# ToneControl-BC547.net
KiCad netlist of a schematic drawn in EAGLE
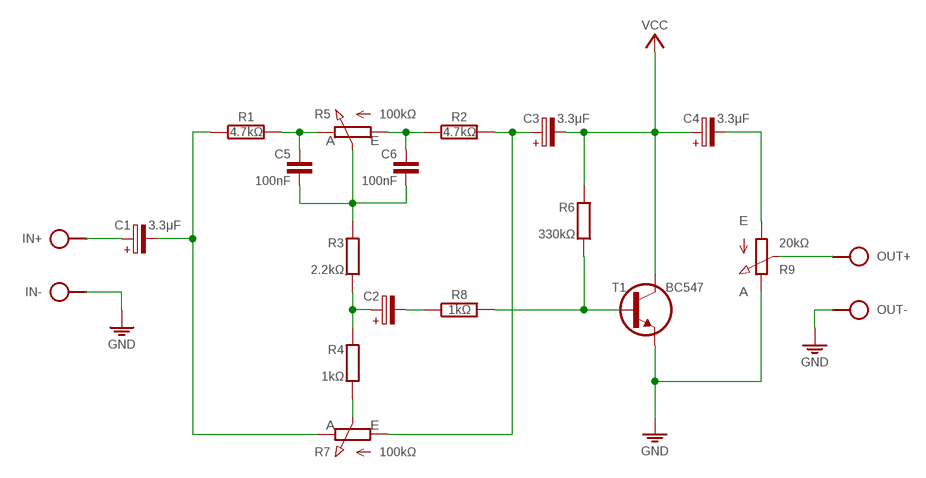
[diagram p0: schematic, sheet 1]

(export (version "E")
  (design (tool "Eeschema 10.0.6"))
  (components
    (comp (ref "C1")
      (value "3.3μF")
      (footprint "eagle-import:E2,5-3")
      (libsource (lib "eagle-import") (part "CPOL-HE2,5-3"))
    )
    (comp (ref "C2")
      (value "CPOL-HE2,5-3")
      (footprint "eagle-import:E2,5-3")
      (libsource (lib "eagle-import") (part "CPOL-HE2,5-3"))
    )
    (comp (ref "C3")
      (value "3.3μF")
      (footprint "eagle-import:E2,5-3")
      (libsource (lib "eagle-import") (part "CPOL-HE2,5-3"))
    )
    (comp (ref "C4")
      (value "3.3μF")
      (footprint "eagle-import:E2,5-3")
      (libsource (lib "eagle-import") (part "CPOL-HE2,5-3"))
    )
    (comp (ref "C5")
      (value "100nF")
      (footprint "eagle-import:C050-020X044_V")
      (libsource (lib "eagle-import") (part "C050-020X044/V"))
    )
    (comp (ref "C6")
      (value "100nF")
      (footprint "eagle-import:C050-020X044_V")
      (libsource (lib "eagle-import") (part "C050-020X044/V"))
    )
    (comp (ref "IN")
      (value "SPAD+--+")
      (footprint "eagle-import:SPAD-+")
      (libsource (lib "eagle-import") (part "SPAD+--+"))
    )
    (comp (ref "OUT")
      (value "SPAD+-+-")
      (footprint "eagle-import:SPAD+-")
      (libsource (lib "eagle-import") (part "SPAD+-+-"))
    )
    (comp (ref "R1")
      (value "4.7kΩ")
      (footprint "eagle-import:0204_10")
      (libsource (lib "eagle-import") (part "R-H0204/10"))
    )
    (comp (ref "R2")
      (value "4.7kΩ")
      (footprint "eagle-import:0204_10")
      (libsource (lib "eagle-import") (part "R-H0204/10"))
    )
    (comp (ref "R3")
      (value "2.2kΩ")
      (footprint "eagle-import:0204_10-V")
      (libsource (lib "eagle-import") (part "R0204/10-V"))
    )
    (comp (ref "R4")
      (value "1kΩ")
      (footprint "eagle-import:0204_10-V")
      (libsource (lib "eagle-import") (part "R0204/10-V"))
    )
    (comp (ref "R5")
      (value "100kΩ")
      (footprint "eagle-import:POT")
      (libsource (lib "eagle-import") (part "POT-H"))
    )
    (comp (ref "R6")
      (value "330kΩ")
      (footprint "eagle-import:0204_10-V")
      (libsource (lib "eagle-import") (part "R0204/10-V"))
    )
    (comp (ref "R7")
      (value "100kΩ")
      (footprint "eagle-import:POT")
      (libsource (lib "eagle-import") (part "POT-H"))
    )
    (comp (ref "R8")
      (value "1kΩ")
      (footprint "eagle-import:0204_10")
      (libsource (lib "eagle-import") (part "R-H0204/10"))
    )
    (comp (ref "R9")
      (value "20kΩ")
      (footprint "eagle-import:POT")
      (libsource (lib "eagle-import") (part "POT"))
    )
    (comp (ref "S1")
      (value "VCC_GNDR")
      (footprint "eagle-import:SPAD+-")
      (libsource (lib "eagle-import") (part "VCC_GNDR"))
    )
    (comp (ref "T1")
      (value "BC547")
      (footprint "eagle-import:TO92-CBE")
      (libsource (lib "eagle-import") (part "BC547CBE"))
    )
  )
  (nets
    (net (code "1") (name "GND") (class "Default")
      (node (ref "IN") (pin "1") (pinfunction "P$1_1") (pintype "passive"))
      (node (ref "OUT") (pin "1") (pinfunction "P$1_1") (pintype "passive"))
      (node (ref "R9") (pin "E") (pinfunction "E_E") (pintype "passive"))
      (node (ref "S1") (pin "1") (pinfunction "GND_1") (pintype "power_in"))
      (node (ref "T1") (pin "E") (pinfunction "E_E") (pintype "passive"))
    )
    (net (code "2") (name "Net-(C1-Pad-)") (class "Default")
      (node (ref "C1") (pin "-") (pinfunction "-_-") (pintype "passive"))
      (node (ref "R1") (pin "1") (pinfunction "1_1") (pintype "passive"))
      (node (ref "R7") (pin "E") (pinfunction "E_E") (pintype "passive"))
    )
    (net (code "3") (name "Net-(C2-Pad+)") (class "Default")
      (node (ref "C2") (pin "+") (pinfunction "+_+") (pintype "passive"))
      (node (ref "R3") (pin "2") (pinfunction "2_2") (pintype "passive"))
      (node (ref "R4") (pin "1") (pinfunction "1_1") (pintype "passive"))
    )
    (net (code "4") (name "Net-(C2-Pad-)") (class "Default")
      (node (ref "C2") (pin "-") (pinfunction "-_-") (pintype "passive"))
      (node (ref "R8") (pin "1") (pinfunction "1_1") (pintype "passive"))
    )
    (net (code "5") (name "Net-(C3-Pad+)") (class "Default")
      (node (ref "C3") (pin "+") (pinfunction "+_+") (pintype "passive"))
      (node (ref "R2") (pin "2") (pinfunction "2_2") (pintype "passive"))
      (node (ref "R7") (pin "A") (pinfunction "A_A") (pintype "passive"))
    )
    (net (code "6") (name "Net-(C4-Pad-)") (class "Default")
      (node (ref "C4") (pin "-") (pinfunction "-_-") (pintype "passive"))
      (node (ref "R9") (pin "A") (pinfunction "A_A") (pintype "passive"))
    )
    (net (code "7") (name "Net-(C5-Pad1)") (class "Default")
      (node (ref "C5") (pin "1") (pinfunction "1_1") (pintype "passive"))
      (node (ref "R1") (pin "2") (pinfunction "2_2") (pintype "passive"))
      (node (ref "R5") (pin "E") (pinfunction "E_E") (pintype "passive"))
    )
    (net (code "8") (name "Net-(C5-Pad2)") (class "Default")
      (node (ref "C5") (pin "2") (pinfunction "2_2") (pintype "passive"))
      (node (ref "C6") (pin "2") (pinfunction "2_2") (pintype "passive"))
      (node (ref "R3") (pin "1") (pinfunction "1_1") (pintype "passive"))
      (node (ref "R5") (pin "S") (pinfunction "S_S") (pintype "passive"))
    )
    (net (code "9") (name "Net-(C6-Pad1)") (class "Default")
      (node (ref "C6") (pin "1") (pinfunction "1_1") (pintype "passive"))
      (node (ref "R2") (pin "1") (pinfunction "1_1") (pintype "passive"))
      (node (ref "R5") (pin "A") (pinfunction "A_A") (pintype "passive"))
    )
    (net (code "10") (name "Net-(INA-P$1)") (class "Default")
      (node (ref "C1") (pin "+") (pinfunction "+_+") (pintype "passive"))
      (node (ref "IN") (pin "2") (pinfunction "P$1_2") (pintype "passive"))
    )
    (net (code "11") (name "Net-(OUTA-P$1)") (class "Default")
      (node (ref "OUT") (pin "2") (pinfunction "P$1_2") (pintype "passive"))
      (node (ref "R9") (pin "S") (pinfunction "S_S") (pintype "passive"))
    )
    (net (code "12") (name "Net-(R4-Pad2)") (class "Default")
      (node (ref "R4") (pin "2") (pinfunction "2_2") (pintype "passive"))
      (node (ref "R7") (pin "S") (pinfunction "S_S") (pintype "passive"))
    )
    (net (code "13") (name "Net-(R6-Pad2)") (class "Default")
      (node (ref "R6") (pin "2") (pinfunction "2_2") (pintype "passive"))
      (node (ref "R8") (pin "2") (pinfunction "2_2") (pintype "passive"))
      (node (ref "T1") (pin "B") (pinfunction "B_B") (pintype "passive"))
    )
    (net (code "14") (name "Net-(S1A-VCC)") (class "Default")
      (node (ref "C3") (pin "-") (pinfunction "-_-") (pintype "passive"))
      (node (ref "C4") (pin "+") (pinfunction "+_+") (pintype "passive"))
      (node (ref "R6") (pin "1") (pinfunction "1_1") (pintype "passive"))
      (node (ref "S1") (pin "2") (pinfunction "VCC_2") (pintype "power_in"))
      (node (ref "T1") (pin "C") (pinfunction "C_C") (pintype "passive"))
    )
  )
)
